# Power.net
KiCad netlist of a schematic drawn in EAGLE
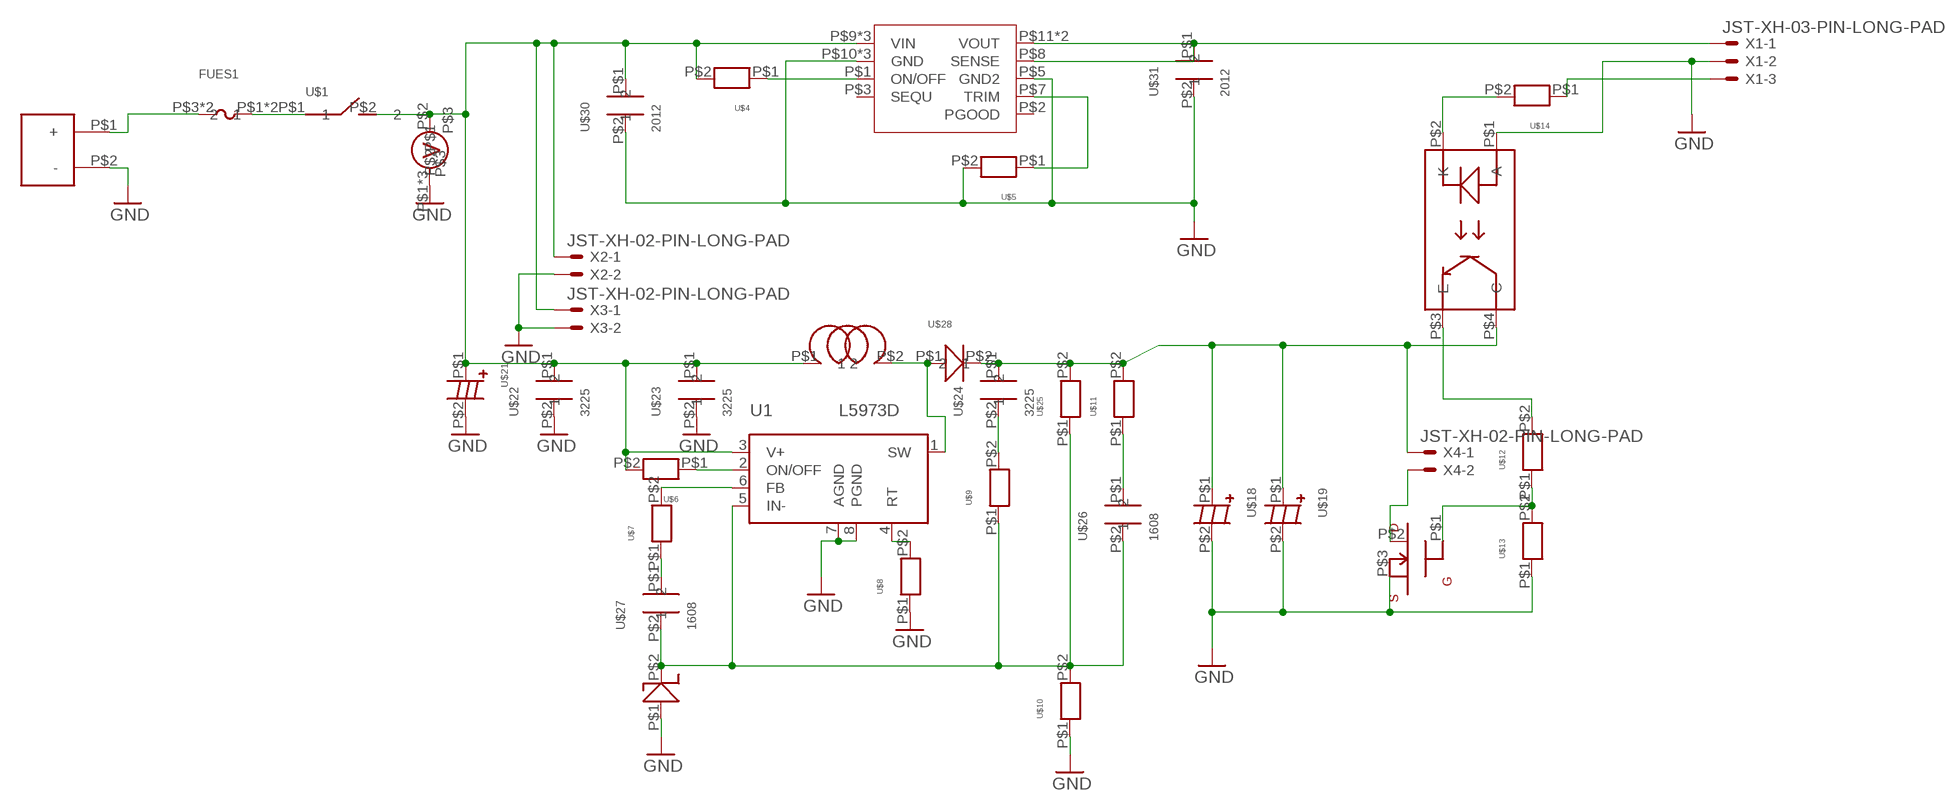
[diagram p0: schematic, sheet 1]

(export (version "E")
  (design (tool "Eeschema 10.0.6"))
  (components
    (comp (ref "FUES1")
      (value "FUSE")
      (footprint "eagle-import:FUSE")
      (libsource (lib "eagle-import") (part "FUSE"))
    )
    (comp (ref "U$1") (value "SW") (footprint "eagle-import:SW") (libsource (lib "eagle-import") (part "SW")))
    (comp (ref "U$2") (value "V") (footprint "eagle-import:V") (libsource (lib "eagle-import") (part "V")))
    (comp (ref "U$3")
      (value "DCDC")
      (footprint "eagle-import:DC-DC")
      (libsource (lib "eagle-import") (part "DCDC"))
    )
    (comp (ref "U$4") (value "R") (footprint "eagle-import:1608") (libsource (lib "eagle-import") (part "R")))
    (comp (ref "U$5") (value "R") (footprint "eagle-import:1608") (libsource (lib "eagle-import") (part "R")))
    (comp (ref "U$6") (value "R") (footprint "eagle-import:1608") (libsource (lib "eagle-import") (part "R")))
    (comp (ref "U$7") (value "R") (footprint "eagle-import:1608") (libsource (lib "eagle-import") (part "R")))
    (comp (ref "U$8") (value "R") (footprint "eagle-import:1608") (libsource (lib "eagle-import") (part "R")))
    (comp (ref "U$9") (value "R") (footprint "eagle-import:1608") (libsource (lib "eagle-import") (part "R")))
    (comp (ref "U$10")
      (value "R")
      (footprint "eagle-import:1608")
      (libsource (lib "eagle-import") (part "R"))
    )
    (comp (ref "U$11")
      (value "R")
      (footprint "eagle-import:1608")
      (libsource (lib "eagle-import") (part "R"))
    )
    (comp (ref "U$12")
      (value "R")
      (footprint "eagle-import:1608")
      (libsource (lib "eagle-import") (part "R"))
    )
    (comp (ref "U$13")
      (value "R")
      (footprint "eagle-import:1608")
      (libsource (lib "eagle-import") (part "R"))
    )
    (comp (ref "U$14")
      (value "R")
      (footprint "eagle-import:1608")
      (libsource (lib "eagle-import") (part "R"))
    )
    (comp (ref "U$15")
      (value "PHOTOCOUPLER")
      (footprint "eagle-import:PHOTOCOUPLER")
      (libsource (lib "eagle-import") (part "PHOTOCOUPLER"))
    )
    (comp (ref "U$16")
      (value "XT60")
      (footprint "eagle-import:XT60")
      (libsource (lib "eagle-import") (part "XT60"))
    )
    (comp (ref "U$17")
      (value "MOS")
      (footprint "eagle-import:MOS")
      (libsource (lib "eagle-import") (part "MOS"))
    )
    (comp (ref "U$18") (value "C") (footprint "eagle-import:C") (libsource (lib "eagle-import") (part "C")))
    (comp (ref "U$19") (value "C") (footprint "eagle-import:C") (libsource (lib "eagle-import") (part "C")))
    (comp (ref "U$20") (value "I") (footprint "eagle-import:I") (libsource (lib "eagle-import") (part "I")))
    (comp (ref "U$21")
      (value "C")
      (footprint "eagle-import:C")
      (libsource (lib "eagle-import") (part "C 47uF 25V_C"))
    )
    (comp (ref "U$22")
      (value "3225")
      (footprint "eagle-import:3225")
      (libsource (lib "eagle-import") (part "3225"))
    )
    (comp (ref "U$23")
      (value "3225")
      (footprint "eagle-import:3225")
      (libsource (lib "eagle-import") (part "3225"))
    )
    (comp (ref "U$24")
      (value "3225")
      (footprint "eagle-import:3225")
      (libsource (lib "eagle-import") (part "3225"))
    )
    (comp (ref "U$25")
      (value "R")
      (footprint "eagle-import:1608")
      (libsource (lib "eagle-import") (part "R"))
    )
    (comp (ref "U$26")
      (value "1608")
      (footprint "eagle-import:CON")
      (libsource (lib "eagle-import") (part "1608"))
    )
    (comp (ref "U$27")
      (value "1608")
      (footprint "eagle-import:CON")
      (libsource (lib "eagle-import") (part "1608"))
    )
    (comp (ref "U$28") (value "D") (footprint "eagle-import:D") (libsource (lib "eagle-import") (part "D")))
    (comp (ref "U$29")
      (value "TD")
      (footprint "eagle-import:TD")
      (libsource (lib "eagle-import") (part "TD"))
    )
    (comp (ref "U$30")
      (value "2012")
      (footprint "eagle-import:2012")
      (libsource (lib "eagle-import") (part "2012"))
    )
    (comp (ref "U$31")
      (value "2012")
      (footprint "eagle-import:2012")
      (libsource (lib "eagle-import") (part "2012"))
    )
    (comp (ref "U1")
      (value "L5973D")
      (footprint "eagle-import:HSOP8")
      (libsource (lib "eagle-import") (part "L5973D"))
    )
    (comp (ref "X1")
      (value "JST-XH-03-PIN-LONG-PAD")
      (footprint "eagle-import:JST-XH-03-PACKAGE-LONG-PAD")
      (libsource (lib "eagle-import") (part "JST-XH-03-PIN-LONG-PAD"))
    )
    (comp (ref "X2")
      (value "JST-XH-02-PIN-LONG-PAD")
      (footprint "eagle-import:JST-XH-02-PACKAGE-LONG-PAD")
      (libsource (lib "eagle-import") (part "JST-XH-02-PIN-LONG-PAD"))
    )
    (comp (ref "X3")
      (value "JST-XH-02-PIN-LONG-PAD")
      (footprint "eagle-import:JST-XH-02-PACKAGE-LONG-PAD")
      (libsource (lib "eagle-import") (part "JST-XH-02-PIN-LONG-PAD"))
    )
    (comp (ref "X4")
      (value "JST-XH-02-PIN-LONG-PAD")
      (footprint "eagle-import:JST-XH-02-PACKAGE-LONG-PAD")
      (libsource (lib "eagle-import") (part "JST-XH-02-PIN-LONG-PAD"))
    )
  )
  (nets
    (net (code "1") (name "GND") (class "Default")
      (node (ref "U$10") (pin "P$1") (pinfunction "P$1_P$1") (pintype "bidirectional"))
      (node (ref "U$13") (pin "P$1") (pinfunction "P$1_P$1") (pintype "bidirectional"))
      (node (ref "U$15") (pin "P$1") (pinfunction "A_P$1") (pintype "bidirectional"))
      (node (ref "U$16") (pin "P$2") (pinfunction "-_P$2") (pintype "bidirectional"))
      (node (ref "U$17") (pin "P$3") (pinfunction "P$2_P$3") (pintype "bidirectional"))
      (node (ref "U$18") (pin "P$2") (pinfunction "P$2_P$2") (pintype "bidirectional"))
      (node (ref "U$19") (pin "P$2") (pinfunction "P$2_P$2") (pintype "bidirectional"))
      (node (ref "U$2") (pin "P$1") (pinfunction "P$1_P$1") (pintype "bidirectional"))
      (node (ref "U$2") (pin "P$4") (pinfunction "P$1_P$4") (pintype "bidirectional"))
      (node (ref "U$2") (pin "P$5") (pinfunction "P$1_P$5") (pintype "bidirectional"))
      (node (ref "U$21") (pin "P$2") (pinfunction "P$2_P$2") (pintype "bidirectional"))
      (node (ref "U$22") (pin "P$2") (pinfunction "2_P$2") (pintype "bidirectional"))
      (node (ref "U$23") (pin "P$2") (pinfunction "2_P$2") (pintype "bidirectional"))
      (node (ref "U$29") (pin "P$1") (pinfunction "P$1_P$1") (pintype "bidirectional"))
      (node (ref "U$3") (pin "P$10") (pinfunction "GND_P$10") (pintype "bidirectional"))
      (node (ref "U$3") (pin "P$16") (pinfunction "GND_P$16") (pintype "bidirectional"))
      (node (ref "U$3") (pin "P$17") (pinfunction "GND_P$17") (pintype "bidirectional"))
      (node (ref "U$3") (pin "P$5") (pinfunction "GND2_P$5") (pintype "bidirectional"))
      (node (ref "U$30") (pin "P$2") (pinfunction "2_P$2") (pintype "bidirectional"))
      (node (ref "U$31") (pin "P$2") (pinfunction "2_P$2") (pintype "bidirectional"))
      (node (ref "U$5") (pin "P$2") (pinfunction "P$2_P$2") (pintype "bidirectional"))
      (node (ref "U$8") (pin "P$1") (pinfunction "P$1_P$1") (pintype "bidirectional"))
      (node (ref "U1") (pin "7") (pinfunction "AGND_7") (pintype "power_in"))
      (node (ref "U1") (pin "8") (pinfunction "PGND_8") (pintype "power_in"))
      (node (ref "X1") (pin "2") (pinfunction "S_2") (pintype "passive"))
      (node (ref "X2") (pin "2") (pinfunction "S_2") (pintype "passive"))
      (node (ref "X3") (pin "2") (pinfunction "S_2") (pintype "passive"))
    )
    (net (code "2") (name "Net-(U$1-1)") (class "Default")
      (node (ref "FUES1") (pin "P$1") (pinfunction "2_P$1") (pintype "bidirectional"))
      (node (ref "FUES1") (pin "P$2") (pinfunction "2_P$2") (pintype "bidirectional"))
      (node (ref "U$1") (pin "P$1") (pinfunction "1_P$1") (pintype "bidirectional"))
    )
    (net (code "3") (name "Net-(U$1-2)") (class "Default")
      (node (ref "U$1") (pin "P$2") (pinfunction "2_P$2") (pintype "bidirectional"))
      (node (ref "U$2") (pin "P$2") (pinfunction "P$2_P$2") (pintype "bidirectional"))
      (node (ref "U$20") (pin "P$1") (pinfunction "1_P$1") (pintype "bidirectional"))
      (node (ref "U$21") (pin "P$1") (pinfunction "P$1_P$1") (pintype "bidirectional"))
      (node (ref "U$22") (pin "P$1") (pinfunction "1_P$1") (pintype "bidirectional"))
      (node (ref "U$23") (pin "P$1") (pinfunction "1_P$1") (pintype "bidirectional"))
      (node (ref "U$3") (pin "P$14") (pinfunction "VIN_P$14") (pintype "bidirectional"))
      (node (ref "U$3") (pin "P$15") (pinfunction "VIN_P$15") (pintype "bidirectional"))
      (node (ref "U$3") (pin "P$9") (pinfunction "VIN_P$9") (pintype "bidirectional"))
      (node (ref "U$30") (pin "P$1") (pinfunction "1_P$1") (pintype "bidirectional"))
      (node (ref "U$4") (pin "P$2") (pinfunction "P$2_P$2") (pintype "bidirectional"))
      (node (ref "U$6") (pin "P$2") (pinfunction "P$2_P$2") (pintype "bidirectional"))
      (node (ref "U1") (pin "3") (pinfunction "V+_3") (pintype "input"))
      (node (ref "X2") (pin "1") (pinfunction "S_1") (pintype "passive"))
      (node (ref "X3") (pin "1") (pinfunction "S_1") (pintype "passive"))
    )
    (net (code "4") (name "Net-(U$3-ON{slash}OFF)") (class "Default")
      (node (ref "U$3") (pin "P$1") (pinfunction "ON/OFF_P$1") (pintype "bidirectional"))
      (node (ref "U$4") (pin "P$1") (pinfunction "P$1_P$1") (pintype "bidirectional"))
    )
    (net (code "5") (name "Net-(U$3-SENSE)") (class "Default")
      (node (ref "U$3") (pin "P$11") (pinfunction "VOUT_P$11") (pintype "bidirectional"))
      (node (ref "U$3") (pin "P$18") (pinfunction "VOUT_P$18") (pintype "bidirectional"))
      (node (ref "U$3") (pin "P$8") (pinfunction "SENSE_P$8") (pintype "bidirectional"))
      (node (ref "U$31") (pin "P$1") (pinfunction "1_P$1") (pintype "bidirectional"))
      (node (ref "X1") (pin "1") (pinfunction "S_1") (pintype "passive"))
    )
    (net (code "6") (name "Net-(U$3-TRIM)") (class "Default")
      (node (ref "U$3") (pin "P$7") (pinfunction "TRIM_P$7") (pintype "bidirectional"))
      (node (ref "U$5") (pin "P$1") (pinfunction "P$1_P$1") (pintype "bidirectional"))
    )
    (net (code "7") (name "Net-(U$15-C)") (class "Default")
      (node (ref "U$11") (pin "P$2") (pinfunction "P$2_P$2") (pintype "bidirectional"))
      (node (ref "U$15") (pin "P$4") (pinfunction "C_P$4") (pintype "bidirectional"))
      (node (ref "U$18") (pin "P$1") (pinfunction "P$1_P$1") (pintype "bidirectional"))
      (node (ref "U$19") (pin "P$1") (pinfunction "P$1_P$1") (pintype "bidirectional"))
      (node (ref "U$24") (pin "P$1") (pinfunction "1_P$1") (pintype "bidirectional"))
      (node (ref "U$25") (pin "P$2") (pinfunction "P$2_P$2") (pintype "bidirectional"))
      (node (ref "U$28") (pin "P$2") (pinfunction "2_P$2") (pintype "bidirectional"))
      (node (ref "X4") (pin "1") (pinfunction "S_1") (pintype "passive"))
    )
    (net (code "8") (name "Net-(U$15-E)") (class "Default")
      (node (ref "U$12") (pin "P$2") (pinfunction "P$2_P$2") (pintype "bidirectional"))
      (node (ref "U$15") (pin "P$3") (pinfunction "E_P$3") (pintype "bidirectional"))
    )
    (net (code "9") (name "Net-(U$15-K)") (class "Default")
      (node (ref "U$14") (pin "P$2") (pinfunction "P$2_P$2") (pintype "bidirectional"))
      (node (ref "U$15") (pin "P$2") (pinfunction "K_P$2") (pintype "bidirectional"))
    )
    (net (code "10") (name "Net-(U$16-+)") (class "Default")
      (node (ref "FUES1") (pin "P$3") (pinfunction "1_P$3") (pintype "bidirectional"))
      (node (ref "FUES1") (pin "P$4") (pinfunction "1_P$4") (pintype "bidirectional"))
      (node (ref "U$16") (pin "P$1") (pinfunction "+_P$1") (pintype "bidirectional"))
    )
    (net (code "11") (name "Net-(U$17-P$1)") (class "Default")
      (node (ref "U$17") (pin "P$2") (pinfunction "P$1_P$2") (pintype "bidirectional"))
      (node (ref "X4") (pin "2") (pinfunction "S_2") (pintype "passive"))
    )
    (net (code "12") (name "Net-(U$17-P$3)") (class "Default")
      (node (ref "U$12") (pin "P$1") (pinfunction "P$1_P$1") (pintype "bidirectional"))
      (node (ref "U$13") (pin "P$2") (pinfunction "P$2_P$2") (pintype "bidirectional"))
      (node (ref "U$17") (pin "P$1") (pinfunction "P$3_P$1") (pintype "bidirectional"))
    )
    (net (code "13") (name "Net-(U$20-2)") (class "Default")
      (node (ref "U$20") (pin "P$2") (pinfunction "2_P$2") (pintype "bidirectional"))
      (node (ref "U$28") (pin "P$1") (pinfunction "1_P$1") (pintype "bidirectional"))
      (node (ref "U1") (pin "1") (pinfunction "SW_1") (pintype "power_in"))
    )
    (net (code "14") (name "Net-(U$24-2)") (class "Default")
      (node (ref "U$24") (pin "P$2") (pinfunction "2_P$2") (pintype "bidirectional"))
      (node (ref "U$9") (pin "P$2") (pinfunction "P$2_P$2") (pintype "bidirectional"))
    )
    (net (code "15") (name "Net-(U$26-1)") (class "Default")
      (node (ref "U$11") (pin "P$1") (pinfunction "P$1_P$1") (pintype "bidirectional"))
      (node (ref "U$26") (pin "P$1") (pinfunction "1_P$1") (pintype "bidirectional"))
    )
    (net (code "16") (name "Net-(U$26-2)") (class "Default")
      (node (ref "U$10") (pin "P$2") (pinfunction "P$2_P$2") (pintype "bidirectional"))
      (node (ref "U$25") (pin "P$1") (pinfunction "P$1_P$1") (pintype "bidirectional"))
      (node (ref "U$26") (pin "P$2") (pinfunction "2_P$2") (pintype "bidirectional"))
      (node (ref "U$27") (pin "P$2") (pinfunction "2_P$2") (pintype "bidirectional"))
      (node (ref "U$29") (pin "P$2") (pinfunction "P$2_P$2") (pintype "bidirectional"))
      (node (ref "U$9") (pin "P$1") (pinfunction "P$1_P$1") (pintype "bidirectional"))
      (node (ref "U1") (pin "5") (pinfunction "IN-_5") (pintype "input"))
    )
    (net (code "17") (name "Net-(U$27-1)") (class "Default")
      (node (ref "U$27") (pin "P$1") (pinfunction "1_P$1") (pintype "bidirectional"))
      (node (ref "U$7") (pin "P$1") (pinfunction "P$1_P$1") (pintype "bidirectional"))
    )
    (net (code "18") (name "Net-(U1A-FB)") (class "Default")
      (node (ref "U$7") (pin "P$2") (pinfunction "P$2_P$2") (pintype "bidirectional"))
      (node (ref "U1") (pin "6") (pinfunction "FB_6") (pintype "output"))
    )
    (net (code "19") (name "Net-(U1A-ON{slash}OFF)") (class "Default")
      (node (ref "U$6") (pin "P$1") (pinfunction "P$1_P$1") (pintype "bidirectional"))
      (node (ref "U1") (pin "2") (pinfunction "ON/OFF_2") (pintype "bidirectional"))
    )
    (net (code "20") (name "Net-(U1A-RT)") (class "Default")
      (node (ref "U$8") (pin "P$2") (pinfunction "P$2_P$2") (pintype "bidirectional"))
      (node (ref "U1") (pin "4") (pinfunction "RT_4") (pintype "output"))
    )
    (net (code "21") (name "Net-(X1C-S)") (class "Default")
      (node (ref "U$14") (pin "P$1") (pinfunction "P$1_P$1") (pintype "bidirectional"))
      (node (ref "X1") (pin "3") (pinfunction "S_3") (pintype "passive"))
    )
    (net (code "22") (name "unconnected-(U$2-PadP$3)") (class "Default")
      (node (ref "U$2") (pin "P$3") (pinfunction "P$3_P$3") (pintype "bidirectional"))
    )
    (net (code "23") (name "unconnected-(U$3-PGOOD-PadP$2)") (class "Default")
      (node (ref "U$3") (pin "P$2") (pinfunction "PGOOD_P$2") (pintype "bidirectional"))
    )
    (net (code "24") (name "unconnected-(U$3-SEQU-PadP$3)") (class "Default")
      (node (ref "U$3") (pin "P$3") (pinfunction "SEQU_P$3") (pintype "bidirectional"))
    )
  )
)
